# SAMC21_Xplained_Pro_Target_MCU.net
KiCad netlist of a schematic drawn in Altium Designer
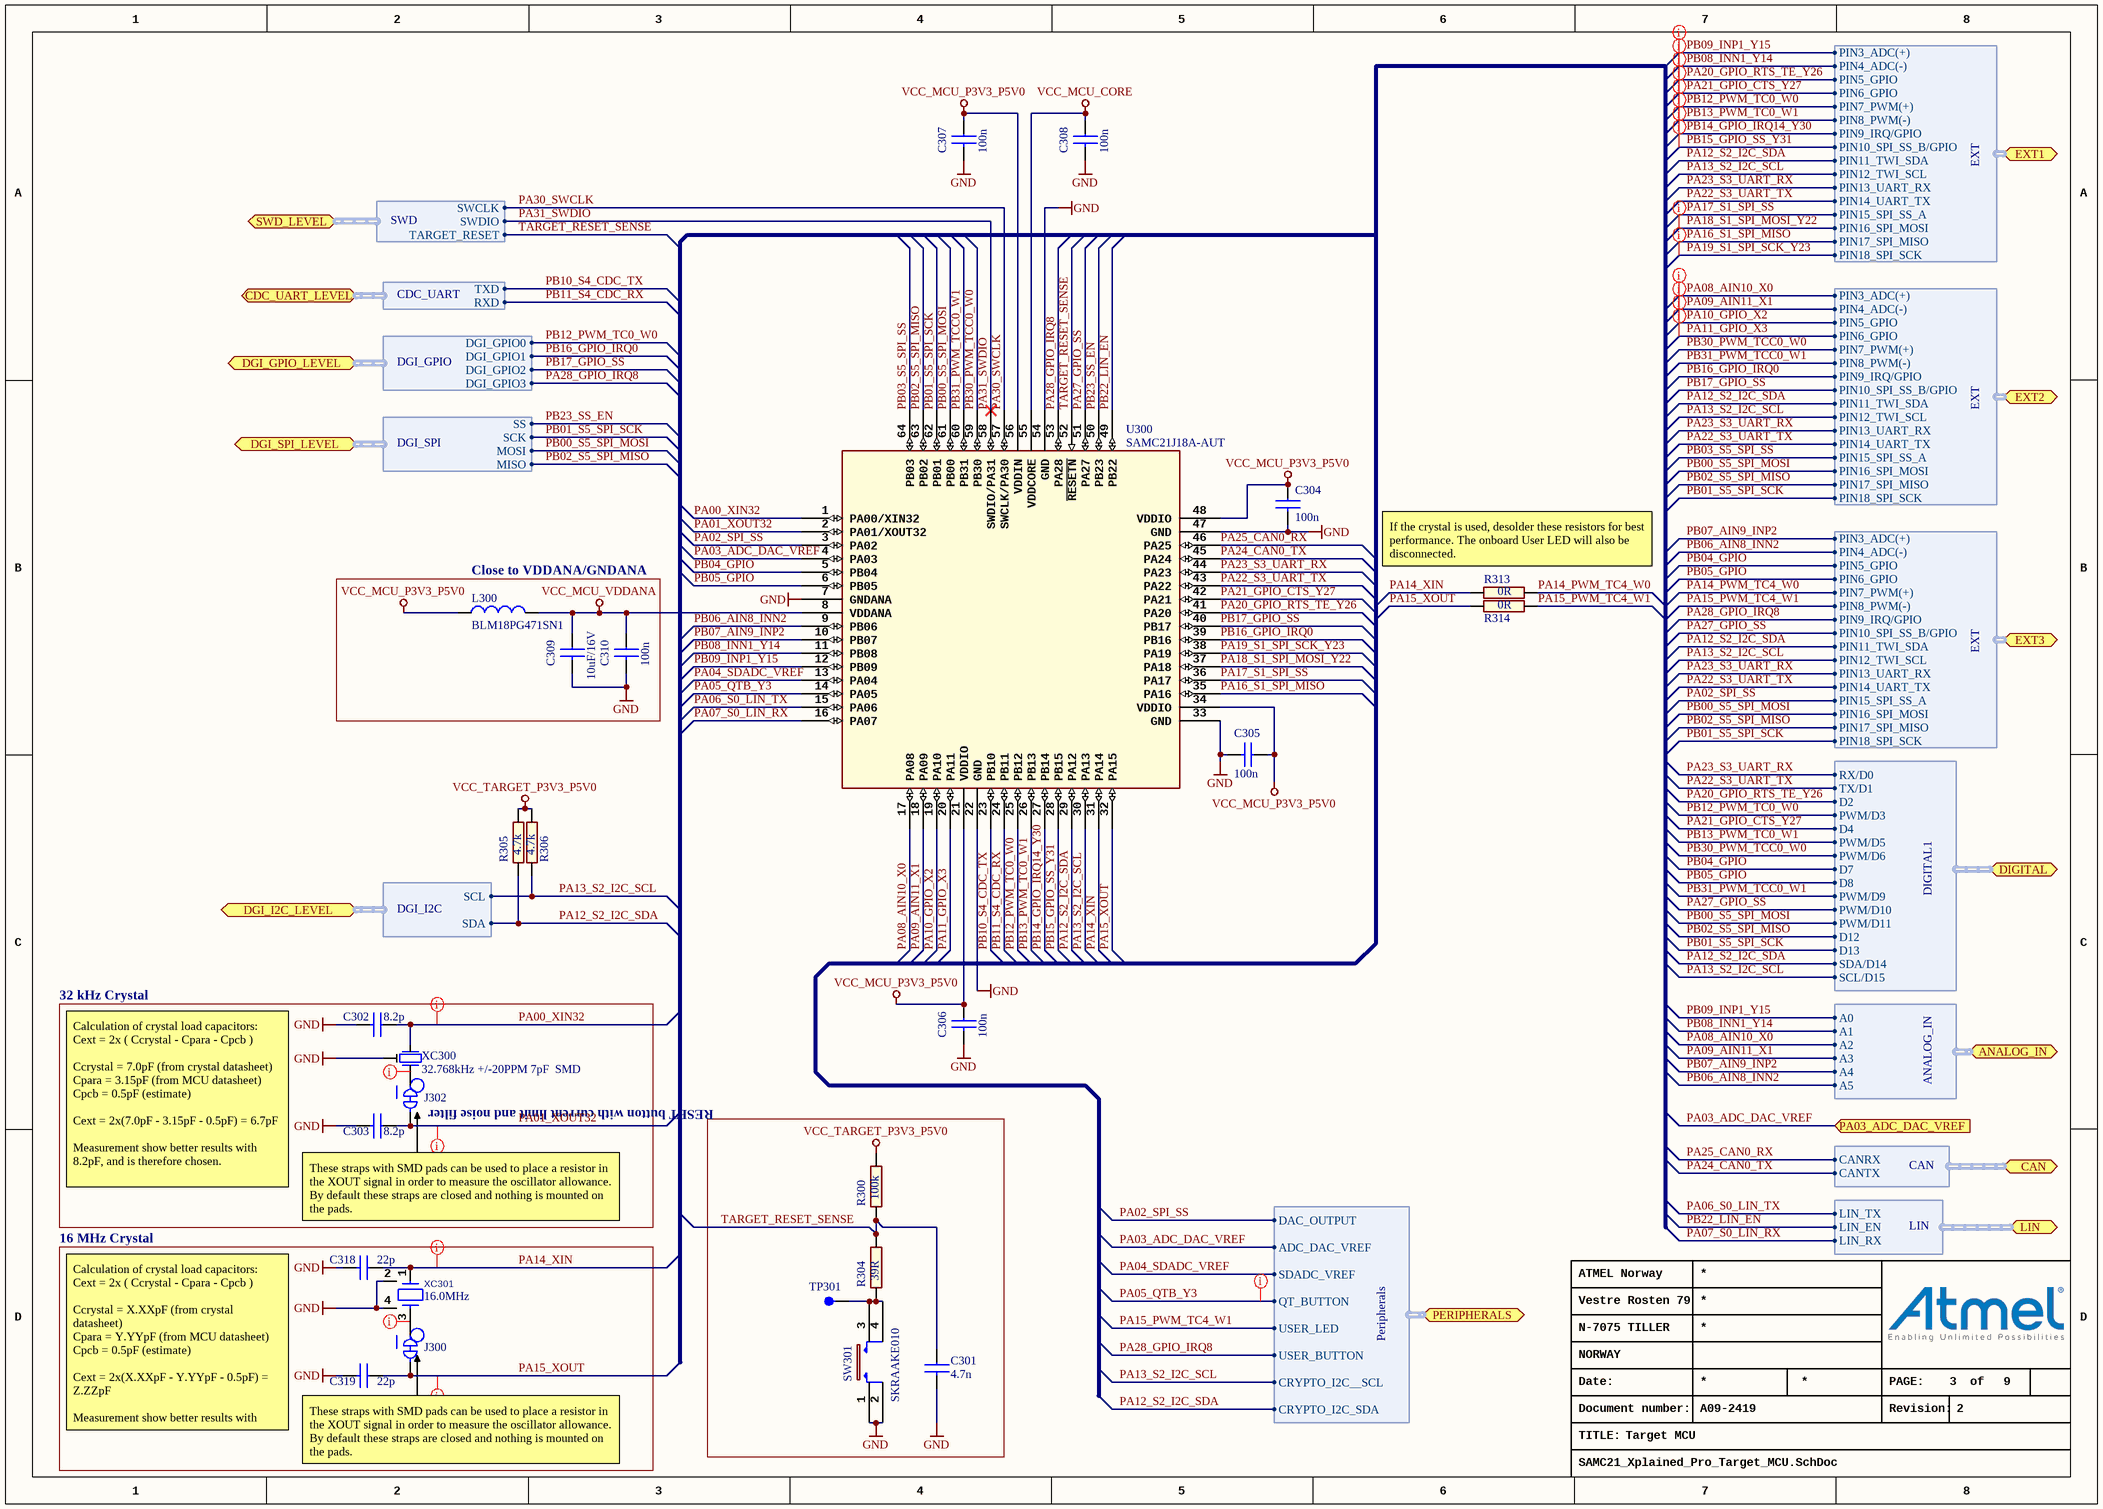
[diagram p0: SAMC21_Xplained_Pro_Target_MCU.SchDoc]

(export (version "E")
  (design (tool "Eeschema 10.0.6"))
  (components
    (comp (ref "C301")
      (value "4.7n")
      (footprint "AP1-00001")
      (description "Ceramic capacitor, SMD 0402, X7R, 25V, +/-10% (de35287)")
      (fields (field (name "TOLERANCE") "25V, +/-10%") (field (name "Comment") "CAP-NONPOL"))
      (libsource (lib "AltiumDbLib") (part "CAP-NONPOL"))
    )
    (comp (ref "C302")
      (value "8.2p")
      (footprint "AP1-00001")
      (description "Ceramic capacitor, SMD 0402, NP0, 50V, +/-5%")
      (fields (field (name "TOLERANCE") "50V, +/-5%") (field (name "Comment") "CAP-NONPOL"))
      (libsource (lib "AltiumDbLib") (part "CAP-NONPOL"))
    )
    (comp (ref "C303")
      (value "8.2p")
      (footprint "AP1-00001")
      (description "Ceramic capacitor, SMD 0402, NP0, 50V, +/-5%")
      (fields (field (name "TOLERANCE") "50V, +/-5%") (field (name "Comment") "CAP-NONPOL"))
      (libsource (lib "AltiumDbLib") (part "CAP-NONPOL"))
    )
    (comp (ref "C304")
      (value "100n")
      (footprint "AP1-00001")
      (description "Ceramic capacitor, SMD 0402, X7R, 16V, +/-10%")
      (fields (field (name "TOLERANCE") "16V, +/-10%") (field (name "MANUFACTURER") "Kemet"))
      (libsource (lib "AltiumDbLib") (part "CAP-NONPOL"))
    )
    (comp (ref "C305")
      (value "100n")
      (footprint "AP1-00001")
      (description "Ceramic capacitor, SMD 0402, X7R, 16V, +/-10%")
      (fields (field (name "TOLERANCE") "16V, +/-10%") (field (name "MANUFACTURER") "Kemet"))
      (libsource (lib "AltiumDbLib") (part "CAP-NONPOL"))
    )
    (comp (ref "C306")
      (value "100n")
      (footprint "AP1-00001")
      (description "Ceramic capacitor, SMD 0402, X7R, 16V, +/-10%")
      (fields (field (name "TOLERANCE") "16V, +/-10%") (field (name "MANUFACTURER") "Kemet"))
      (libsource (lib "AltiumDbLib") (part "CAP-NONPOL"))
    )
    (comp (ref "C307")
      (value "100n")
      (footprint "AP1-00001")
      (description "Ceramic capacitor, SMD 0402, X7R, 16V, +/-10%")
      (fields (field (name "TOLERANCE") "16V, +/-10%") (field (name "MANUFACTURER") "Kemet"))
      (libsource (lib "AltiumDbLib") (part "CAP-NONPOL"))
    )
    (comp (ref "C308")
      (value "100n")
      (footprint "AP1-00001")
      (description "Ceramic capacitor, SMD 0402, X7R, 16V, +/-10%")
      (fields (field (name "TOLERANCE") "16V, +/-10%") (field (name "MANUFACTURER") "Kemet"))
      (libsource (lib "AltiumDbLib") (part "CAP-NONPOL"))
    )
    (comp (ref "C309")
      (value "10uF/16V")
      (footprint "AP1-00039")
      (description "Ceramic capacitor, SMD 0603, X5R, 16V, 10UF ± 20% (High Density)")
      (fields (field (name "MANUFACTURER") "Taiyo Yuden") (field (name "MPN") "EMK107BBJ106MA-T"))
      (libsource (lib "AltiumDbLib") (part "CAP-NONPOL"))
    )
    (comp (ref "C310")
      (value "100n")
      (footprint "AP1-00001")
      (description "Ceramic capacitor, SMD 0402, X7R, 16V, +/-10%")
      (fields (field (name "TOLERANCE") "16V, +/-10%") (field (name "MANUFACTURER") "Kemet"))
      (libsource (lib "AltiumDbLib") (part "CAP-NONPOL"))
    )
    (comp (ref "C318")
      (value "22p")
      (footprint "AP1-00001")
      (description "Ceramic capacitor, SMD 0402, NP0, 50V, +/-5%")
      (fields (field (name "TOLERANCE") "50V, +/-5%") (field (name "Comment") "CAP-NONPOL"))
      (libsource (lib "AltiumDbLib") (part "CAP-NONPOL"))
    )
    (comp (ref "C319")
      (value "22p")
      (footprint "AP1-00001")
      (description "Ceramic capacitor, SMD 0402, NP0, 50V, +/-5%")
      (fields (field (name "TOLERANCE") "50V, +/-5%") (field (name "Comment") "CAP-NONPOL"))
      (libsource (lib "AltiumDbLib") (part "CAP-NONPOL"))
    )
    (comp (ref "J300")
      (value "~")
      (footprint "AP9-00044")
      (description "Default closed SMD strap, 0603 size")
      (libsource (lib "AltiumDbLib") (part "SMD-STRAP_CLOSED"))
    )
    (comp (ref "J302")
      (value "~")
      (footprint "AP9-00044")
      (description "Default closed SMD strap, 0603 size")
      (libsource (lib "AltiumDbLib") (part "SMD-STRAP_CLOSED"))
    )
    (comp (ref "L300")
      (value "BLM18PG471SN1")
      (footprint "AP3-00005")
      (description "SMD RF inductor 0603. Z=470Ohm (@100MHz), Max R(dc)=0.65Ohm, Max current=1A")
      (fields (field (name "TOLERANCE") "±25%") (field (name "MANUFACTURER") "Murata"))
      (libsource (lib "AltiumDbLib") (part "INDUCTOR"))
    )
    (comp (ref "R300")
      (value "100k")
      (footprint "AP2-00011")
      (description "Thick film resistor, SMD 0402, 1/16W, 1%")
      (fields (field (name "TOLERANCE") "1 %") (field (name "Comment") "R2"))
      (libsource (lib "AltiumDbLib") (part "R2"))
    )
    (comp (ref "R304")
      (value "39R")
      (footprint "AP2-00011")
      (description "Thick film resistor, SMD 0402, 1/16W, 1%")
      (fields (field (name "TOLERANCE") "1 %") (field (name "Comment") "R2"))
      (libsource (lib "") (part "R2_1"))
    )
    (comp (ref "R305")
      (value "4.7k")
      (footprint "AP2-00000")
      (description "Thick film resistor, SMD 0402, 1/16W, 1%")
      (fields (field (name "TOLERANCE") "1 %") (field (name "Comment") "R2"))
      (libsource (lib "AltiumDbLib") (part "R2"))
    )
    (comp (ref "R306")
      (value "4.7k")
      (footprint "AP2-00000")
      (description "Thick film resistor, SMD 0402, 1/16W, 1%")
      (fields (field (name "TOLERANCE") "1 %") (field (name "Comment") "R2"))
      (libsource (lib "AltiumDbLib") (part "R2"))
    )
    (comp (ref "R313")
      (value "0R")
      (footprint "AP2-00000")
      (description "Thick film resistor, SMD 0402, 1/16W, 1%")
      (fields (field (name "TOLERANCE") "1 %") (field (name "Comment") "R2"))
      (libsource (lib "") (part "R2_2"))
    )
    (comp (ref "R314")
      (value "0R")
      (footprint "AP2-00000")
      (description "Thick film resistor, SMD 0402, 1/16W, 1%")
      (fields (field (name "TOLERANCE") "1 %") (field (name "Comment") "R2"))
      (libsource (lib "") (part "R2_2"))
    )
    (comp (ref "SW301")
      (value "SKRAAKE010")
      (footprint "AP8-00137")
      (description "6.2x6.2 mm SMD tact switch, same as A08-0091 but less force is needed")
      (fields
        (field (name "MANUFACTURER") "ALPS")
        (field (name "Comment") "Can be ordered in low volumes from Mouser")
      )
      (libsource (lib "AltiumDbLib") (part "PUSHBUTTON1"))
    )
    (comp (ref "TP301")
      (value "TESTPOINT")
      (footprint "AP8-00010")
      (description "Single SMD testpad")
      (libsource (lib "AltiumDbLib") (part "TESTPOINT"))
    )
    (comp (ref "U300")
      (value "SAMC21J18A-AUT")
      (footprint "AP6-00173")
      (description "Atmel 32-bit RISC MCU 64pin")
      (fields (field (name "MANUFACTURER") "ATMEL") (field (name "Comment") "SAMC21J_TQFP64"))
      (libsource (lib "AltiumDbLib") (part "SAMC21J_TQFP64"))
    )
    (comp (ref "XC300")
      (value "32.768kHz +/-20PPM 7pF  SMD")
      (footprint "AP7-00044")
      (description "32k768 crystal, +-20ppm, CL=7pF, max ESR 60kOhm, SMD")
      (fields (field (name "TOLERANCE") "+/- 20 PPM") (field (name "MANUFACTURER") "Micro Crystal"))
      (libsource (lib "AltiumDbLib") (part "CRYSTAL_2P_metal"))
    )
    (comp (ref "XC301")
      (value "16.0MHz")
      (footprint "AP7-00061")
      (description "16MHz uXtal, 3.2 x 2.5 mm SMD, CL=9pF, 15PPM, ESR=80ohm(Max.")
      (fields (field (name "TOLERANCE") "15ppm") (field (name "MANUFACTURER") "Epson Toyocom"))
      (libsource (lib "AltiumDbLib") (part "TSX-3225"))
    )
  )
  (nets
    (net (code "12") (name "/PA00_XIN32") (class "Default")
      (node (ref "C302") (pin "1") (pinfunction "1_1") (pintype "passive"))
      (node (ref "U300") (pin "1") (pinfunction "PA00/XIN32_1") (pintype "bidirectional"))
      (node (ref "XC300") (pin "2") (pinfunction "2_2") (pintype "passive"))
    )
    (net (code "13") (name "/PA01_XOUT32") (class "Default")
      (node (ref "C303") (pin "1") (pinfunction "1_1") (pintype "passive"))
      (node (ref "J302") (pin "2") (pinfunction "2_2") (pintype "passive"))
      (node (ref "U300") (pin "2") (pinfunction "PA01/XOUT32_2") (pintype "bidirectional"))
    )
    (net (code "14") (name "/PA02_SPI_SS") (class "Default")
      (node (ref "U300") (pin "3") (pinfunction "PA02_3") (pintype "bidirectional"))
    )
    (net (code "15") (name "/PA03_ADC_DAC_VREF") (class "Default")
      (node (ref "U300") (pin "4") (pinfunction "PA03_4") (pintype "bidirectional"))
    )
    (net (code "16") (name "/PA04_SDADC_VREF") (class "Default")
      (node (ref "U300") (pin "13") (pinfunction "PA04_13") (pintype "bidirectional"))
    )
    (net (code "17") (name "/PA05_QTB_Y3") (class "Default")
      (node (ref "U300") (pin "14") (pinfunction "PA05_14") (pintype "bidirectional"))
    )
    (net (code "18") (name "/PA06_S0_LIN_TX") (class "Default")
      (node (ref "U300") (pin "15") (pinfunction "PA06_15") (pintype "bidirectional"))
    )
    (net (code "19") (name "/PA07_S0_LIN_RX") (class "Default")
      (node (ref "U300") (pin "16") (pinfunction "PA07_16") (pintype "bidirectional"))
    )
    (net (code "20") (name "/PA08_AIN10_X0") (class "Default")
      (node (ref "U300") (pin "17") (pinfunction "PA08_17") (pintype "bidirectional"))
    )
    (net (code "21") (name "/PA09_AIN11_X1") (class "Default")
      (node (ref "U300") (pin "18") (pinfunction "PA09_18") (pintype "bidirectional"))
    )
    (net (code "22") (name "/PA10_GPIO_X2") (class "Default")
      (node (ref "U300") (pin "19") (pinfunction "PA10_19") (pintype "bidirectional"))
    )
    (net (code "23") (name "/PA11_GPIO_X3") (class "Default")
      (node (ref "U300") (pin "20") (pinfunction "PA11_20") (pintype "bidirectional"))
    )
    (net (code "24") (name "/PA12_S2_I2C_SDA") (class "Default")
      (node (ref "R305") (pin "1") (pinfunction "1_1") (pintype "passive"))
      (node (ref "U300") (pin "29") (pinfunction "PA12_29") (pintype "bidirectional"))
    )
    (net (code "25") (name "/PA13_S2_I2C_SCL") (class "Default")
      (node (ref "R306") (pin "1") (pinfunction "1_1") (pintype "passive"))
      (node (ref "U300") (pin "30") (pinfunction "PA13_30") (pintype "bidirectional"))
    )
    (net (code "26") (name "/PA14_PWM_TC4_W0") (class "Default")
      (node (ref "R313") (pin "2") (pinfunction "2_2") (pintype "passive"))
    )
    (net (code "27") (name "/PA14_XIN") (class "Default")
      (node (ref "C318") (pin "1") (pinfunction "1_1") (pintype "passive"))
      (node (ref "R313") (pin "1") (pinfunction "1_1") (pintype "passive"))
      (node (ref "U300") (pin "31") (pinfunction "PA14_31") (pintype "bidirectional"))
      (node (ref "XC301") (pin "1") (pinfunction "IN_1") (pintype "passive"))
    )
    (net (code "28") (name "/PA15_PWM_TC4_W1") (class "Default")
      (node (ref "R314") (pin "2") (pinfunction "2_2") (pintype "passive"))
    )
    (net (code "29") (name "/PA15_XOUT") (class "Default")
      (node (ref "C319") (pin "1") (pinfunction "1_1") (pintype "passive"))
      (node (ref "J300") (pin "2") (pinfunction "2_2") (pintype "passive"))
      (node (ref "R314") (pin "1") (pinfunction "1_1") (pintype "passive"))
      (node (ref "U300") (pin "32") (pinfunction "PA15_32") (pintype "bidirectional"))
    )
    (net (code "30") (name "/PA16_S1_SPI_MISO") (class "Default")
      (node (ref "U300") (pin "35") (pinfunction "PA16_35") (pintype "bidirectional"))
    )
    (net (code "31") (name "/PA17_S1_SPI_SS") (class "Default")
      (node (ref "U300") (pin "36") (pinfunction "PA17_36") (pintype "bidirectional"))
    )
    (net (code "32") (name "/PA18_S1_SPI_MOSI_Y22") (class "Default")
      (node (ref "U300") (pin "37") (pinfunction "PA18_37") (pintype "bidirectional"))
    )
    (net (code "33") (name "/PA19_S1_SPI_SCK_Y23") (class "Default")
      (node (ref "U300") (pin "38") (pinfunction "PA19_38") (pintype "bidirectional"))
    )
    (net (code "34") (name "/PA20_GPIO_RTS_TE_Y26") (class "Default")
      (node (ref "U300") (pin "41") (pinfunction "PA20_41") (pintype "bidirectional"))
    )
    (net (code "35") (name "/PA21_GPIO_CTS_Y27") (class "Default")
      (node (ref "U300") (pin "42") (pinfunction "PA21_42") (pintype "bidirectional"))
    )
    (net (code "36") (name "/PA22_S3_UART_TX") (class "Default")
      (node (ref "U300") (pin "43") (pinfunction "PA22_43") (pintype "bidirectional"))
    )
    (net (code "37") (name "/PA23_S3_UART_RX") (class "Default")
      (node (ref "U300") (pin "44") (pinfunction "PA23_44") (pintype "bidirectional"))
    )
    (net (code "38") (name "/PA24_CAN0_TX") (class "Default")
      (node (ref "U300") (pin "45") (pinfunction "PA24_45") (pintype "bidirectional"))
    )
    (net (code "39") (name "/PA25_CAN0_RX") (class "Default")
      (node (ref "U300") (pin "46") (pinfunction "PA25_46") (pintype "bidirectional"))
    )
    (net (code "40") (name "/PA27_GPIO_SS") (class "Default")
      (node (ref "U300") (pin "51") (pinfunction "PA27_51") (pintype "bidirectional"))
    )
    (net (code "41") (name "/PA28_GPIO_IRQ8") (class "Default")
      (node (ref "U300") (pin "53") (pinfunction "PA28_53") (pintype "bidirectional"))
    )
    (net (code "42") (name "/PA30_SWCLK") (class "Default")
      (node (ref "U300") (pin "57") (pinfunction "SWCLK/PA30_57") (pintype "bidirectional"))
    )
    (net (code "43") (name "/PA31_SWDIO") (class "Default")
      (node (ref "U300") (pin "58") (pinfunction "SWDIO/PA31_58") (pintype "bidirectional+no_connect"))
    )
    (net (code "44") (name "/PB00_S5_SPI_MOSI") (class "Default")
      (node (ref "U300") (pin "61") (pinfunction "PB00_61") (pintype "bidirectional"))
    )
    (net (code "45") (name "/PB01_S5_SPI_SCK") (class "Default")
      (node (ref "U300") (pin "62") (pinfunction "PB01_62") (pintype "bidirectional"))
    )
    (net (code "46") (name "/PB02_S5_SPI_MISO") (class "Default")
      (node (ref "U300") (pin "63") (pinfunction "PB02_63") (pintype "bidirectional"))
    )
    (net (code "47") (name "/PB03_S5_SPI_SS") (class "Default")
      (node (ref "U300") (pin "64") (pinfunction "PB03_64") (pintype "bidirectional"))
    )
    (net (code "48") (name "/PB04_GPIO") (class "Default")
      (node (ref "U300") (pin "5") (pinfunction "PB04_5") (pintype "bidirectional"))
    )
    (net (code "49") (name "/PB05_GPIO") (class "Default")
      (node (ref "U300") (pin "6") (pinfunction "PB05_6") (pintype "bidirectional"))
    )
    (net (code "50") (name "/PB06_AIN8_INN2") (class "Default")
      (node (ref "U300") (pin "9") (pinfunction "PB06_9") (pintype "bidirectional"))
    )
    (net (code "51") (name "/PB07_AIN9_INP2") (class "Default")
      (node (ref "U300") (pin "10") (pinfunction "PB07_10") (pintype "bidirectional"))
    )
    (net (code "52") (name "/PB08_INN1_Y14") (class "Default")
      (node (ref "U300") (pin "11") (pinfunction "PB08_11") (pintype "bidirectional"))
    )
    (net (code "53") (name "/PB09_INP1_Y15") (class "Default")
      (node (ref "U300") (pin "12") (pinfunction "PB09_12") (pintype "bidirectional"))
    )
    (net (code "54") (name "/PB10_S4_CDC_TX") (class "Default")
      (node (ref "U300") (pin "23") (pinfunction "PB10_23") (pintype "bidirectional"))
    )
    (net (code "55") (name "/PB11_S4_CDC_RX") (class "Default")
      (node (ref "U300") (pin "24") (pinfunction "PB11_24") (pintype "bidirectional"))
    )
    (net (code "56") (name "/PB12_PWM_TC0_W0") (class "Default")
      (node (ref "U300") (pin "25") (pinfunction "PB12_25") (pintype "bidirectional"))
    )
    (net (code "57") (name "/PB13_PWM_TC0_W1") (class "Default")
      (node (ref "U300") (pin "26") (pinfunction "PB13_26") (pintype "bidirectional"))
    )
    (net (code "58") (name "/PB14_GPIO_IRQ14_Y30") (class "Default")
      (node (ref "U300") (pin "27") (pinfunction "PB14_27") (pintype "bidirectional"))
    )
    (net (code "59") (name "/PB15_GPIO_SS_Y31") (class "Default")
      (node (ref "U300") (pin "28") (pinfunction "PB15_28") (pintype "bidirectional"))
    )
    (net (code "60") (name "/PB16_GPIO_IRQ0") (class "Default")
      (node (ref "U300") (pin "39") (pinfunction "PB16_39") (pintype "bidirectional"))
    )
    (net (code "61") (name "/PB17_GPIO_SS") (class "Default")
      (node (ref "U300") (pin "40") (pinfunction "PB17_40") (pintype "bidirectional"))
    )
    (net (code "62") (name "/PB22_LIN_EN") (class "Default")
      (node (ref "U300") (pin "49") (pinfunction "PB22_49") (pintype "bidirectional"))
    )
    (net (code "63") (name "/PB23_SS_EN") (class "Default")
      (node (ref "U300") (pin "50") (pinfunction "PB23_50") (pintype "bidirectional"))
    )
    (net (code "64") (name "/PB30_PWM_TCC0_W0") (class "Default")
      (node (ref "U300") (pin "59") (pinfunction "PB30_59") (pintype "bidirectional"))
    )
    (net (code "65") (name "/PB31_PWM_TCC0_W1") (class "Default")
      (node (ref "U300") (pin "60") (pinfunction "PB31_60") (pintype "bidirectional"))
    )
    (net (code "66") (name "/TARGET_RESET_SENSE") (class "Default")
      (node (ref "C301") (pin "1") (pinfunction "1_1") (pintype "passive"))
      (node (ref "R300") (pin "1") (pinfunction "1_1") (pintype "passive"))
      (node (ref "R304") (pin "2") (pinfunction "2_2") (pintype "passive"))
      (node (ref "U300") (pin "52") (pinfunction "~{RESETN}_52") (pintype "input"))
    )
    (net (code "78") (name "GND") (class "Default")
      (node (ref "C301") (pin "2") (pinfunction "2_2") (pintype "passive"))
      (node (ref "C302") (pin "2") (pinfunction "2_2") (pintype "passive"))
      (node (ref "C303") (pin "2") (pinfunction "2_2") (pintype "passive"))
      (node (ref "C304") (pin "2") (pinfunction "2_2") (pintype "passive"))
      (node (ref "C305") (pin "2") (pinfunction "2_2") (pintype "passive"))
      (node (ref "C306") (pin "2") (pinfunction "2_2") (pintype "passive"))
      (node (ref "C307") (pin "2") (pinfunction "2_2") (pintype "passive"))
      (node (ref "C308") (pin "2") (pinfunction "2_2") (pintype "passive"))
      (node (ref "C309") (pin "2") (pinfunction "2_2") (pintype "passive"))
      (node (ref "C310") (pin "2") (pinfunction "2_2") (pintype "passive"))
      (node (ref "C318") (pin "2") (pinfunction "2_2") (pintype "passive"))
      (node (ref "C319") (pin "2") (pinfunction "2_2") (pintype "passive"))
      (node (ref "SW301") (pin "1") (pinfunction "1_1") (pintype "passive"))
      (node (ref "SW301") (pin "2") (pinfunction "2_2") (pintype "passive"))
      (node (ref "U300") (pin "22") (pinfunction "GND_22") (pintype "power_in"))
      (node (ref "U300") (pin "33") (pinfunction "GND_33") (pintype "power_in"))
      (node (ref "U300") (pin "47") (pinfunction "GND_47") (pintype "power_in"))
      (node (ref "U300") (pin "54") (pinfunction "GND_54") (pintype "power_in"))
      (node (ref "U300") (pin "7") (pinfunction "GNDANA_7") (pintype "power_in"))
      (node (ref "XC300") (pin "3") (pinfunction "3_3") (pintype "passive"))
      (node (ref "XC301") (pin "2") (pinfunction "GND_2") (pintype "passive"))
      (node (ref "XC301") (pin "4") (pinfunction "GND_4") (pintype "passive"))
    )
    (net (code "79") (name "Net-(J302-Pad1)") (class "Default")
      (node (ref "J302") (pin "1") (pinfunction "1_1") (pintype "passive"))
      (node (ref "XC300") (pin "1") (pinfunction "1_1") (pintype "passive"))
    )
    (net (code "80") (name "Net-(R304-Pad1)") (class "Default")
      (node (ref "R304") (pin "1") (pinfunction "1_1") (pintype "passive"))
      (node (ref "SW301") (pin "3") (pinfunction "3_3") (pintype "passive"))
      (node (ref "SW301") (pin "4") (pinfunction "4_4") (pintype "passive"))
      (node (ref "TP301") (pin "1") (pinfunction "1_1") (pintype "passive"))
    )
    (net (code "81") (name "Net-(XC301-OUT)") (class "Default")
      (node (ref "J300") (pin "1") (pinfunction "1_1") (pintype "passive"))
      (node (ref "XC301") (pin "3") (pinfunction "OUT_3") (pintype "passive"))
    )
    (net (code "82") (name "VCC_MCU_CORE") (class "Default")
      (node (ref "C308") (pin "1") (pinfunction "1_1") (pintype "passive"))
      (node (ref "U300") (pin "55") (pinfunction "VDDCORE_55") (pintype "power_in"))
    )
    (net (code "83") (name "VCC_MCU_P3V3_P5V0") (class "Default")
      (node (ref "C304") (pin "1") (pinfunction "1_1") (pintype "passive"))
      (node (ref "C305") (pin "1") (pinfunction "1_1") (pintype "passive"))
      (node (ref "C306") (pin "1") (pinfunction "1_1") (pintype "passive"))
      (node (ref "C307") (pin "1") (pinfunction "1_1") (pintype "passive"))
      (node (ref "L300") (pin "1") (pinfunction "1_1") (pintype "passive"))
      (node (ref "U300") (pin "21") (pinfunction "VDDIO_21") (pintype "power_in"))
      (node (ref "U300") (pin "34") (pinfunction "VDDIO_34") (pintype "power_in"))
      (node (ref "U300") (pin "48") (pinfunction "VDDIO_48") (pintype "power_in"))
      (node (ref "U300") (pin "56") (pinfunction "VDDIN_56") (pintype "power_in"))
    )
    (net (code "84") (name "VCC_MCU_VDDANA") (class "Default")
      (node (ref "C309") (pin "1") (pinfunction "1_1") (pintype "passive"))
      (node (ref "C310") (pin "1") (pinfunction "1_1") (pintype "passive"))
      (node (ref "L300") (pin "2") (pinfunction "2_2") (pintype "passive"))
      (node (ref "U300") (pin "8") (pinfunction "VDDANA_8") (pintype "power_in"))
    )
    (net (code "85") (name "VCC_TARGET_P3V3_P5V0") (class "Default")
      (node (ref "R300") (pin "2") (pinfunction "2_2") (pintype "passive"))
      (node (ref "R305") (pin "2") (pinfunction "2_2") (pintype "passive"))
      (node (ref "R306") (pin "2") (pinfunction "2_2") (pintype "passive"))
    )
  )
)
